# FSR_Platform.net
KiCad netlist of a schematic drawn in EAGLE
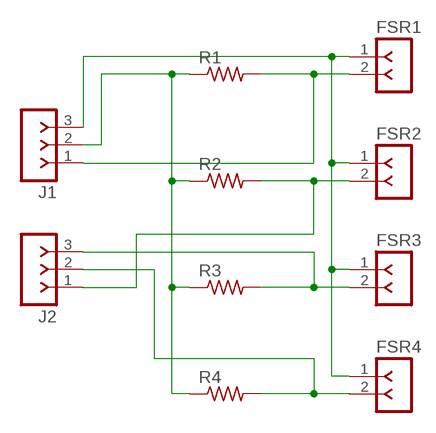
[diagram p0: schematic, sheet 1]

(export (version "E")
  (design (tool "Eeschema 10.0.6"))
  (components
    (comp (ref "FSR1")
      (value "FSR-5''")
      (footprint "eagle-import:FSR-5''")
      (libsource (lib "eagle-import") (part "FSR-5''"))
    )
    (comp (ref "FSR2")
      (value "FSR-5''")
      (footprint "eagle-import:FSR-5''")
      (libsource (lib "eagle-import") (part "FSR-5''"))
    )
    (comp (ref "FSR3")
      (value "FSR-5''")
      (footprint "eagle-import:FSR-5''")
      (libsource (lib "eagle-import") (part "FSR-5''"))
    )
    (comp (ref "FSR4")
      (value "FSR-5''")
      (footprint "eagle-import:FSR-5''")
      (libsource (lib "eagle-import") (part "FSR-5''"))
    )
    (comp (ref "J1")
      (value "F-1X03-SIP-100-40")
      (footprint "eagle-import:SIP-100-03-40")
      (libsource (lib "eagle-import") (part "F-1X03-SIP-100-40"))
    )
    (comp (ref "J2")
      (value "F-1X03-SIP-100-40")
      (footprint "eagle-import:SIP-100-03-40")
      (libsource (lib "eagle-import") (part "F-1X03-SIP-100-40"))
    )
    (comp (ref "R1")
      (value "RESISTOR_R-US_0204/5")
      (footprint "eagle-import:RESISTOR_0204_5")
      (libsource (lib "eagle-import") (part "RESISTOR_R-US_0204/5"))
    )
    (comp (ref "R2")
      (value "RESISTOR_R-US_0204/5")
      (footprint "eagle-import:RESISTOR_0204_5")
      (libsource (lib "eagle-import") (part "RESISTOR_R-US_0204/5"))
    )
    (comp (ref "R3")
      (value "RESISTOR_R-US_0204/5")
      (footprint "eagle-import:RESISTOR_0204_5")
      (libsource (lib "eagle-import") (part "RESISTOR_R-US_0204/5"))
    )
    (comp (ref "R4")
      (value "RESISTOR_R-US_0204/5")
      (footprint "eagle-import:RESISTOR_0204_5")
      (libsource (lib "eagle-import") (part "RESISTOR_R-US_0204/5"))
    )
  )
  (nets
    (net (code "1") (name "Net-(FSR1-Pad1)") (class "Default")
      (node (ref "FSR1") (pin "1") (pinfunction "1_1") (pintype "passive"))
      (node (ref "FSR2") (pin "1") (pinfunction "1_1") (pintype "passive"))
      (node (ref "FSR3") (pin "1") (pinfunction "1_1") (pintype "passive"))
      (node (ref "FSR4") (pin "1") (pinfunction "1_1") (pintype "passive"))
      (node (ref "J1") (pin "3") (pinfunction "3_3") (pintype "passive"))
    )
    (net (code "2") (name "Net-(FSR1-Pad2)") (class "Default")
      (node (ref "FSR1") (pin "2") (pinfunction "2_2") (pintype "passive"))
      (node (ref "J1") (pin "1") (pinfunction "1_1") (pintype "passive"))
      (node (ref "R1") (pin "2") (pinfunction "2_2") (pintype "passive"))
    )
    (net (code "3") (name "Net-(FSR2-Pad2)") (class "Default")
      (node (ref "FSR2") (pin "2") (pinfunction "2_2") (pintype "passive"))
      (node (ref "J2") (pin "1") (pinfunction "1_1") (pintype "passive"))
      (node (ref "R2") (pin "2") (pinfunction "2_2") (pintype "passive"))
    )
    (net (code "4") (name "Net-(FSR3-Pad2)") (class "Default")
      (node (ref "FSR3") (pin "2") (pinfunction "2_2") (pintype "passive"))
      (node (ref "J2") (pin "3") (pinfunction "3_3") (pintype "passive"))
      (node (ref "R3") (pin "2") (pinfunction "2_2") (pintype "passive"))
    )
    (net (code "5") (name "Net-(FSR4-Pad2)") (class "Default")
      (node (ref "FSR4") (pin "2") (pinfunction "2_2") (pintype "passive"))
      (node (ref "J2") (pin "2") (pinfunction "2_2") (pintype "passive"))
      (node (ref "R4") (pin "2") (pinfunction "2_2") (pintype "passive"))
    )
    (net (code "6") (name "Net-(J1-Pad2)") (class "Default")
      (node (ref "J1") (pin "2") (pinfunction "2_2") (pintype "passive"))
      (node (ref "R1") (pin "1") (pinfunction "1_1") (pintype "passive"))
      (node (ref "R2") (pin "1") (pinfunction "1_1") (pintype "passive"))
      (node (ref "R3") (pin "1") (pinfunction "1_1") (pintype "passive"))
      (node (ref "R4") (pin "1") (pinfunction "1_1") (pintype "passive"))
    )
  )
)
